# Matrix_keyboard.net
KiCad netlist of a schematic drawn in EAGLE
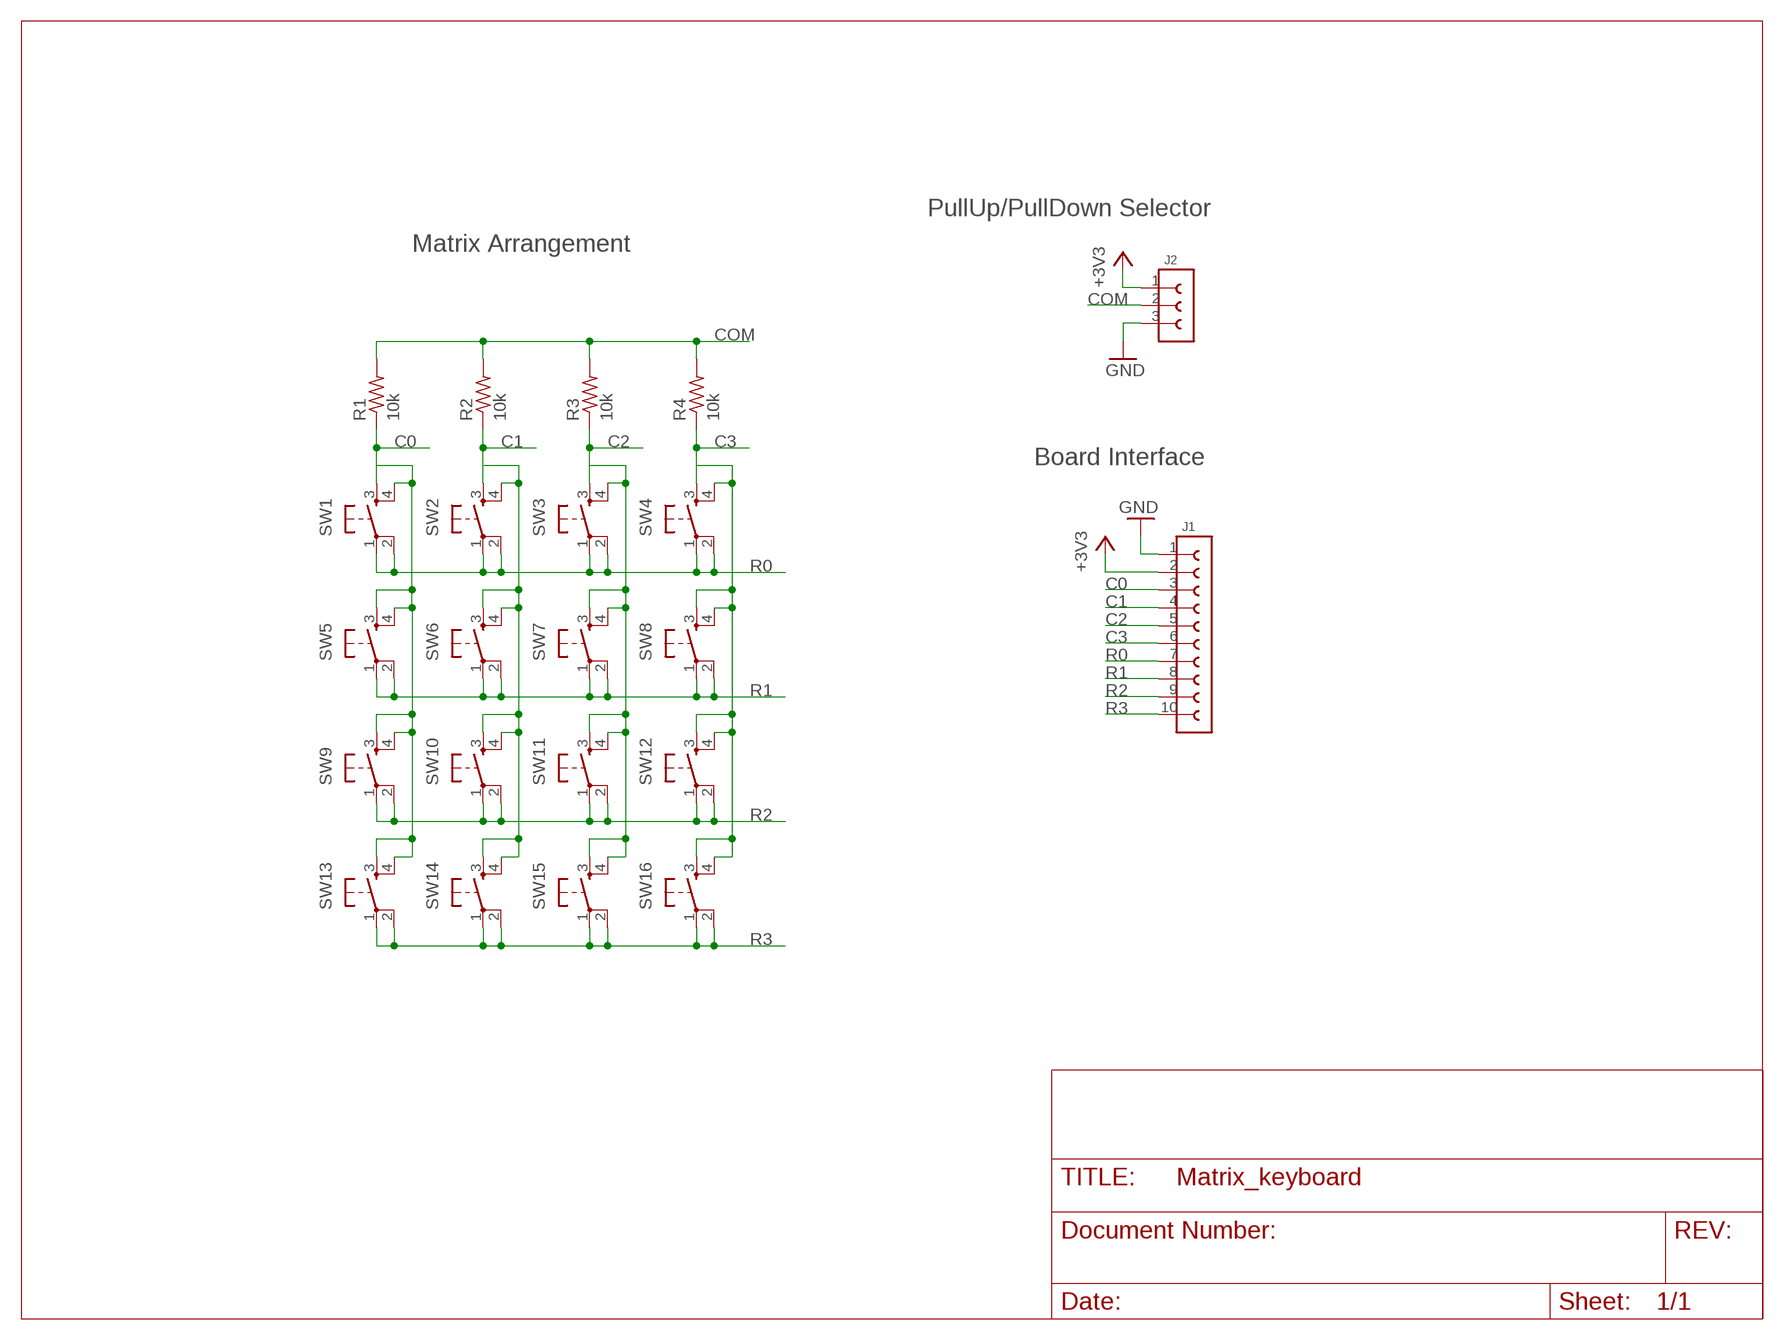
[diagram p0: schematic, sheet 1]

(export (version "E")
  (design (tool "Eeschema 10.0.6"))
  (components
    (comp (ref "J1")
      (value "61301011121")
      (footprint "eagle-import:PHSP254P2540X254X1154-10S")
      (libsource (lib "eagle-import") (part "6130101?1121"))
    )
    (comp (ref "J2")
      (value "61300311121")
      (footprint "eagle-import:PHSP254P762X254X1154-3S")
      (libsource (lib "eagle-import") (part "6130031?1121"))
    )
    (comp (ref "R1")
      (value "10k")
      (footprint "eagle-import:RESC0603")
      (libsource (lib "eagle-import") (part "CRG?0603F10K10"))
    )
    (comp (ref "R2")
      (value "10k")
      (footprint "eagle-import:RESC0603")
      (libsource (lib "eagle-import") (part "CRG?0603F10K10"))
    )
    (comp (ref "R3")
      (value "10k")
      (footprint "eagle-import:RESC0603")
      (libsource (lib "eagle-import") (part "CRG?0603F10K10"))
    )
    (comp (ref "R4")
      (value "10k")
      (footprint "eagle-import:RESC0603")
      (libsource (lib "eagle-import") (part "CRG?0603F10K10"))
    )
    (comp (ref "SW1")
      (value "TL3301NF160QJ")
      (footprint "eagle-import:TACT600X600-4J")
      (fields (field (name "MANUFACTURER") "E-SWITCH"))
      (libsource (lib "eagle-import") (part "TL3301?JNF160Q"))
    )
    (comp (ref "SW2")
      (value "TL3301NF160QJ")
      (footprint "eagle-import:TACT600X600-4J")
      (fields (field (name "MANUFACTURER") "E-SWITCH"))
      (libsource (lib "eagle-import") (part "TL3301?JNF160Q"))
    )
    (comp (ref "SW3")
      (value "TL3301NF160QJ")
      (footprint "eagle-import:TACT600X600-4J")
      (fields (field (name "MANUFACTURER") "E-SWITCH"))
      (libsource (lib "eagle-import") (part "TL3301?JNF160Q"))
    )
    (comp (ref "SW4")
      (value "TL3301NF160QJ")
      (footprint "eagle-import:TACT600X600-4J")
      (fields (field (name "MANUFACTURER") "E-SWITCH"))
      (libsource (lib "eagle-import") (part "TL3301?JNF160Q"))
    )
    (comp (ref "SW5")
      (value "TL3301NF160QJ")
      (footprint "eagle-import:TACT600X600-4J")
      (fields (field (name "MANUFACTURER") "E-SWITCH"))
      (libsource (lib "eagle-import") (part "TL3301?JNF160Q"))
    )
    (comp (ref "SW6")
      (value "TL3301NF160QJ")
      (footprint "eagle-import:TACT600X600-4J")
      (fields (field (name "MANUFACTURER") "E-SWITCH"))
      (libsource (lib "eagle-import") (part "TL3301?JNF160Q"))
    )
    (comp (ref "SW7")
      (value "TL3301NF160QJ")
      (footprint "eagle-import:TACT600X600-4J")
      (fields (field (name "MANUFACTURER") "E-SWITCH"))
      (libsource (lib "eagle-import") (part "TL3301?JNF160Q"))
    )
    (comp (ref "SW8")
      (value "TL3301NF160QJ")
      (footprint "eagle-import:TACT600X600-4J")
      (fields (field (name "MANUFACTURER") "E-SWITCH"))
      (libsource (lib "eagle-import") (part "TL3301?JNF160Q"))
    )
    (comp (ref "SW9")
      (value "TL3301NF160QJ")
      (footprint "eagle-import:TACT600X600-4J")
      (fields (field (name "MANUFACTURER") "E-SWITCH"))
      (libsource (lib "eagle-import") (part "TL3301?JNF160Q"))
    )
    (comp (ref "SW10")
      (value "TL3301NF160QJ")
      (footprint "eagle-import:TACT600X600-4J")
      (fields (field (name "MANUFACTURER") "E-SWITCH"))
      (libsource (lib "eagle-import") (part "TL3301?JNF160Q"))
    )
    (comp (ref "SW11")
      (value "TL3301NF160QJ")
      (footprint "eagle-import:TACT600X600-4J")
      (fields (field (name "MANUFACTURER") "E-SWITCH"))
      (libsource (lib "eagle-import") (part "TL3301?JNF160Q"))
    )
    (comp (ref "SW12")
      (value "TL3301NF160QJ")
      (footprint "eagle-import:TACT600X600-4J")
      (fields (field (name "MANUFACTURER") "E-SWITCH"))
      (libsource (lib "eagle-import") (part "TL3301?JNF160Q"))
    )
    (comp (ref "SW13")
      (value "TL3301NF160QJ")
      (footprint "eagle-import:TACT600X600-4J")
      (fields (field (name "MANUFACTURER") "E-SWITCH"))
      (libsource (lib "eagle-import") (part "TL3301?JNF160Q"))
    )
    (comp (ref "SW14")
      (value "TL3301NF160QJ")
      (footprint "eagle-import:TACT600X600-4J")
      (fields (field (name "MANUFACTURER") "E-SWITCH"))
      (libsource (lib "eagle-import") (part "TL3301?JNF160Q"))
    )
    (comp (ref "SW15")
      (value "TL3301NF160QJ")
      (footprint "eagle-import:TACT600X600-4J")
      (fields (field (name "MANUFACTURER") "E-SWITCH"))
      (libsource (lib "eagle-import") (part "TL3301?JNF160Q"))
    )
    (comp (ref "SW16")
      (value "TL3301NF160QJ")
      (footprint "eagle-import:TACT600X600-4J")
      (fields (field (name "MANUFACTURER") "E-SWITCH"))
      (libsource (lib "eagle-import") (part "TL3301?JNF160Q"))
    )
  )
  (nets
    (net (code "1") (name "+3V3") (class "Default")
      (node (ref "J1") (pin "2") (pinfunction "2_2") (pintype "passive"))
      (node (ref "J2") (pin "1") (pinfunction "1_1") (pintype "passive"))
    )
    (net (code "2") (name "/C0") (class "Default")
      (node (ref "J1") (pin "3") (pinfunction "3_3") (pintype "passive"))
      (node (ref "R1") (pin "P$1") (pinfunction "1_P$1") (pintype "passive"))
      (node (ref "SW1") (pin "3") (pinfunction "S_3") (pintype "passive"))
      (node (ref "SW1") (pin "4") (pinfunction "S1_4") (pintype "passive"))
      (node (ref "SW13") (pin "3") (pinfunction "S_3") (pintype "passive"))
      (node (ref "SW13") (pin "4") (pinfunction "S1_4") (pintype "passive"))
      (node (ref "SW5") (pin "3") (pinfunction "S_3") (pintype "passive"))
      (node (ref "SW5") (pin "4") (pinfunction "S1_4") (pintype "passive"))
      (node (ref "SW9") (pin "3") (pinfunction "S_3") (pintype "passive"))
      (node (ref "SW9") (pin "4") (pinfunction "S1_4") (pintype "passive"))
    )
    (net (code "3") (name "/C1") (class "Default")
      (node (ref "J1") (pin "4") (pinfunction "4_4") (pintype "passive"))
      (node (ref "R2") (pin "P$1") (pinfunction "1_P$1") (pintype "passive"))
      (node (ref "SW10") (pin "3") (pinfunction "S_3") (pintype "passive"))
      (node (ref "SW10") (pin "4") (pinfunction "S1_4") (pintype "passive"))
      (node (ref "SW14") (pin "3") (pinfunction "S_3") (pintype "passive"))
      (node (ref "SW14") (pin "4") (pinfunction "S1_4") (pintype "passive"))
      (node (ref "SW2") (pin "3") (pinfunction "S_3") (pintype "passive"))
      (node (ref "SW2") (pin "4") (pinfunction "S1_4") (pintype "passive"))
      (node (ref "SW6") (pin "3") (pinfunction "S_3") (pintype "passive"))
      (node (ref "SW6") (pin "4") (pinfunction "S1_4") (pintype "passive"))
    )
    (net (code "4") (name "/C2") (class "Default")
      (node (ref "J1") (pin "5") (pinfunction "5_5") (pintype "passive"))
      (node (ref "R3") (pin "P$1") (pinfunction "1_P$1") (pintype "passive"))
      (node (ref "SW11") (pin "3") (pinfunction "S_3") (pintype "passive"))
      (node (ref "SW11") (pin "4") (pinfunction "S1_4") (pintype "passive"))
      (node (ref "SW15") (pin "3") (pinfunction "S_3") (pintype "passive"))
      (node (ref "SW15") (pin "4") (pinfunction "S1_4") (pintype "passive"))
      (node (ref "SW3") (pin "3") (pinfunction "S_3") (pintype "passive"))
      (node (ref "SW3") (pin "4") (pinfunction "S1_4") (pintype "passive"))
      (node (ref "SW7") (pin "3") (pinfunction "S_3") (pintype "passive"))
      (node (ref "SW7") (pin "4") (pinfunction "S1_4") (pintype "passive"))
    )
    (net (code "5") (name "/C3") (class "Default")
      (node (ref "J1") (pin "6") (pinfunction "6_6") (pintype "passive"))
      (node (ref "R4") (pin "P$1") (pinfunction "1_P$1") (pintype "passive"))
      (node (ref "SW12") (pin "3") (pinfunction "S_3") (pintype "passive"))
      (node (ref "SW12") (pin "4") (pinfunction "S1_4") (pintype "passive"))
      (node (ref "SW16") (pin "3") (pinfunction "S_3") (pintype "passive"))
      (node (ref "SW16") (pin "4") (pinfunction "S1_4") (pintype "passive"))
      (node (ref "SW4") (pin "3") (pinfunction "S_3") (pintype "passive"))
      (node (ref "SW4") (pin "4") (pinfunction "S1_4") (pintype "passive"))
      (node (ref "SW8") (pin "3") (pinfunction "S_3") (pintype "passive"))
      (node (ref "SW8") (pin "4") (pinfunction "S1_4") (pintype "passive"))
    )
    (net (code "6") (name "/COM") (class "Default")
      (node (ref "J2") (pin "2") (pinfunction "2_2") (pintype "passive"))
      (node (ref "R1") (pin "P$2") (pinfunction "2_P$2") (pintype "passive"))
      (node (ref "R2") (pin "P$2") (pinfunction "2_P$2") (pintype "passive"))
      (node (ref "R3") (pin "P$2") (pinfunction "2_P$2") (pintype "passive"))
      (node (ref "R4") (pin "P$2") (pinfunction "2_P$2") (pintype "passive"))
    )
    (net (code "7") (name "/R0") (class "Default")
      (node (ref "J1") (pin "7") (pinfunction "7_7") (pintype "passive"))
      (node (ref "SW1") (pin "1") (pinfunction "P_1") (pintype "passive"))
      (node (ref "SW1") (pin "2") (pinfunction "P1_2") (pintype "passive"))
      (node (ref "SW2") (pin "1") (pinfunction "P_1") (pintype "passive"))
      (node (ref "SW2") (pin "2") (pinfunction "P1_2") (pintype "passive"))
      (node (ref "SW3") (pin "1") (pinfunction "P_1") (pintype "passive"))
      (node (ref "SW3") (pin "2") (pinfunction "P1_2") (pintype "passive"))
      (node (ref "SW4") (pin "1") (pinfunction "P_1") (pintype "passive"))
      (node (ref "SW4") (pin "2") (pinfunction "P1_2") (pintype "passive"))
    )
    (net (code "8") (name "/R1") (class "Default")
      (node (ref "J1") (pin "8") (pinfunction "8_8") (pintype "passive"))
      (node (ref "SW5") (pin "1") (pinfunction "P_1") (pintype "passive"))
      (node (ref "SW5") (pin "2") (pinfunction "P1_2") (pintype "passive"))
      (node (ref "SW6") (pin "1") (pinfunction "P_1") (pintype "passive"))
      (node (ref "SW6") (pin "2") (pinfunction "P1_2") (pintype "passive"))
      (node (ref "SW7") (pin "1") (pinfunction "P_1") (pintype "passive"))
      (node (ref "SW7") (pin "2") (pinfunction "P1_2") (pintype "passive"))
      (node (ref "SW8") (pin "1") (pinfunction "P_1") (pintype "passive"))
      (node (ref "SW8") (pin "2") (pinfunction "P1_2") (pintype "passive"))
    )
    (net (code "9") (name "/R2") (class "Default")
      (node (ref "J1") (pin "9") (pinfunction "9_9") (pintype "passive"))
      (node (ref "SW10") (pin "1") (pinfunction "P_1") (pintype "passive"))
      (node (ref "SW10") (pin "2") (pinfunction "P1_2") (pintype "passive"))
      (node (ref "SW11") (pin "1") (pinfunction "P_1") (pintype "passive"))
      (node (ref "SW11") (pin "2") (pinfunction "P1_2") (pintype "passive"))
      (node (ref "SW12") (pin "1") (pinfunction "P_1") (pintype "passive"))
      (node (ref "SW12") (pin "2") (pinfunction "P1_2") (pintype "passive"))
      (node (ref "SW9") (pin "1") (pinfunction "P_1") (pintype "passive"))
      (node (ref "SW9") (pin "2") (pinfunction "P1_2") (pintype "passive"))
    )
    (net (code "10") (name "/R3") (class "Default")
      (node (ref "J1") (pin "10") (pinfunction "10_10") (pintype "passive"))
      (node (ref "SW13") (pin "1") (pinfunction "P_1") (pintype "passive"))
      (node (ref "SW13") (pin "2") (pinfunction "P1_2") (pintype "passive"))
      (node (ref "SW14") (pin "1") (pinfunction "P_1") (pintype "passive"))
      (node (ref "SW14") (pin "2") (pinfunction "P1_2") (pintype "passive"))
      (node (ref "SW15") (pin "1") (pinfunction "P_1") (pintype "passive"))
      (node (ref "SW15") (pin "2") (pinfunction "P1_2") (pintype "passive"))
      (node (ref "SW16") (pin "1") (pinfunction "P_1") (pintype "passive"))
      (node (ref "SW16") (pin "2") (pinfunction "P1_2") (pintype "passive"))
    )
    (net (code "11") (name "GND") (class "Default")
      (node (ref "J1") (pin "1") (pinfunction "1_1") (pintype "passive"))
      (node (ref "J2") (pin "3") (pinfunction "3_3") (pintype "passive"))
    )
  )
)
